# USBFilterQT.net
KiCad netlist of a schematic drawn in EAGLE
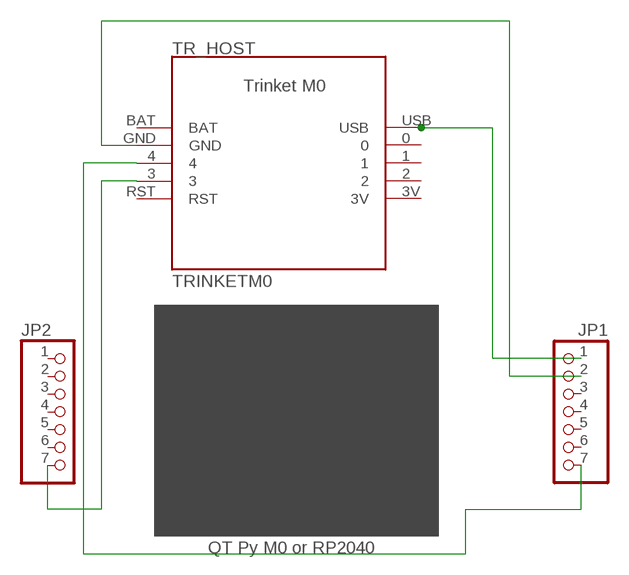
[diagram p0: schematic, sheet 1]

(export (version "E")
  (design (tool "Eeschema 10.0.6"))
  (components
    (comp (ref "JP1")
      (value "PINHD-1X7")
      (footprint "eagle-import:1X07")
      (libsource (lib "eagle-import") (part "PINHD-1X7"))
    )
    (comp (ref "JP2")
      (value "PINHD-1X7")
      (footprint "eagle-import:1X07")
      (libsource (lib "eagle-import") (part "PINHD-1X7"))
    )
    (comp (ref "TR_HOST")
      (value "TRINKETM0")
      (footprint "eagle-import:TRINKET")
      (libsource (lib "eagle-import") (part "TRINKETM0"))
    )
  )
  (nets
    (net (code "1") (name "Net-(JP1-Pad1)") (class "Default")
      (node (ref "JP1") (pin "1") (pinfunction "1_1") (pintype "passive"))
      (node (ref "TR_HOST") (pin "USB") (pinfunction "USB_USB") (pintype "bidirectional"))
    )
    (net (code "2") (name "Net-(JP1-Pad2)") (class "Default")
      (node (ref "JP1") (pin "2") (pinfunction "2_2") (pintype "passive"))
      (node (ref "TR_HOST") (pin "GND") (pinfunction "GND_GND") (pintype "bidirectional"))
    )
    (net (code "3") (name "Net-(JP1-Pad7)") (class "Default")
      (node (ref "JP1") (pin "7") (pinfunction "7_7") (pintype "passive"))
      (node (ref "TR_HOST") (pin "4") (pinfunction "4_4") (pintype "bidirectional"))
    )
    (net (code "4") (name "Net-(JP2-Pad7)") (class "Default")
      (node (ref "JP2") (pin "7") (pinfunction "7_7") (pintype "passive"))
      (node (ref "TR_HOST") (pin "3") (pinfunction "3_3") (pintype "bidirectional"))
    )
    (net (code "5") (name "unconnected-(JP1-Pad3)") (class "Default")
      (node (ref "JP1") (pin "3") (pinfunction "3_3") (pintype "passive"))
    )
    (net (code "6") (name "unconnected-(JP1-Pad4)") (class "Default")
      (node (ref "JP1") (pin "4") (pinfunction "4_4") (pintype "passive"))
    )
    (net (code "7") (name "unconnected-(JP1-Pad5)") (class "Default")
      (node (ref "JP1") (pin "5") (pinfunction "5_5") (pintype "passive"))
    )
    (net (code "8") (name "unconnected-(JP1-Pad6)") (class "Default")
      (node (ref "JP1") (pin "6") (pinfunction "6_6") (pintype "passive"))
    )
    (net (code "9") (name "unconnected-(JP2-Pad1)") (class "Default")
      (node (ref "JP2") (pin "1") (pinfunction "1_1") (pintype "passive"))
    )
    (net (code "10") (name "unconnected-(JP2-Pad2)") (class "Default")
      (node (ref "JP2") (pin "2") (pinfunction "2_2") (pintype "passive"))
    )
    (net (code "11") (name "unconnected-(JP2-Pad3)") (class "Default")
      (node (ref "JP2") (pin "3") (pinfunction "3_3") (pintype "passive"))
    )
    (net (code "12") (name "unconnected-(JP2-Pad4)") (class "Default")
      (node (ref "JP2") (pin "4") (pinfunction "4_4") (pintype "passive"))
    )
    (net (code "13") (name "unconnected-(JP2-Pad5)") (class "Default")
      (node (ref "JP2") (pin "5") (pinfunction "5_5") (pintype "passive"))
    )
    (net (code "14") (name "unconnected-(JP2-Pad6)") (class "Default")
      (node (ref "JP2") (pin "6") (pinfunction "6_6") (pintype "passive"))
    )
    (net (code "15") (name "unconnected-(TR_HOST-Pad0)") (class "Default")
      (node (ref "TR_HOST") (pin "0") (pinfunction "0_0") (pintype "bidirectional"))
    )
    (net (code "16") (name "unconnected-(TR_HOST-Pad1)") (class "Default")
      (node (ref "TR_HOST") (pin "1") (pinfunction "1_1") (pintype "bidirectional"))
    )
    (net (code "17") (name "unconnected-(TR_HOST-Pad2)") (class "Default")
      (node (ref "TR_HOST") (pin "2") (pinfunction "2_2") (pintype "bidirectional"))
    )
    (net (code "18") (name "unconnected-(TR_HOST-Pad3V)") (class "Default")
      (node (ref "TR_HOST") (pin "3V") (pinfunction "3V_3V") (pintype "bidirectional"))
    )
    (net (code "19") (name "unconnected-(TR_HOST-PadBAT)") (class "Default")
      (node (ref "TR_HOST") (pin "BAT") (pinfunction "BAT_BAT") (pintype "bidirectional"))
    )
    (net (code "20") (name "unconnected-(TR_HOST-PadRST)") (class "Default")
      (node (ref "TR_HOST") (pin "RST") (pinfunction "RST_RST") (pintype "bidirectional"))
    )
  )
)
